# AirPort_V1_0.net
KiCad netlist of a schematic drawn in Altium Designer
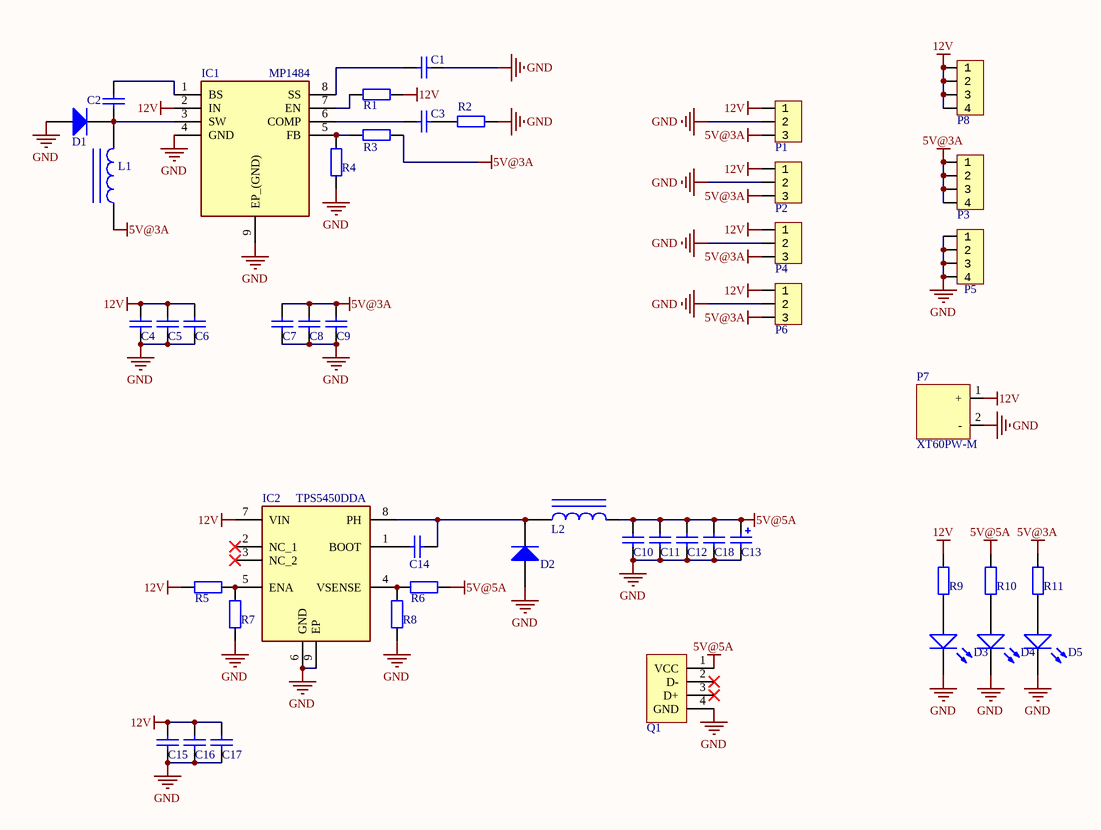
[diagram p0: AirPort_V1.0.SchDoc]

(export (version "E")
  (design (tool "Eeschema 10.0.6"))
  (components
    (comp (ref "C1")
      (value "100nF")
      (footprint "CAP-0603")
      (description "贴片电容")
      (libsource (lib "Power_Lib_Altium") (part "CAP"))
    )
    (comp (ref "C2")
      (value "10nF")
      (footprint "CAP-0603")
      (description "贴片电容")
      (libsource (lib "Power_Lib_Altium") (part "CAP"))
    )
    (comp (ref "C3")
      (value "6.8nF")
      (footprint "CAP-0603")
      (description "贴片电容")
      (libsource (lib "Power_Lib_Altium") (part "CAP"))
    )
    (comp (ref "C4")
      (value "10uF")
      (footprint "CAP-1206")
      (description "贴片电容")
      (libsource (lib "Power_Lib_Altium") (part "CAP"))
    )
    (comp (ref "C5")
      (value "10uF")
      (footprint "CAP-1206")
      (description "贴片电容")
      (libsource (lib "Power_Lib_Altium") (part "CAP"))
    )
    (comp (ref "C6")
      (value "10uF")
      (footprint "CAP-1206")
      (description "贴片电容")
      (libsource (lib "Power_Lib_Altium") (part "CAP"))
    )
    (comp (ref "C7")
      (value "10uF")
      (footprint "CAP-1206")
      (description "贴片电容")
      (libsource (lib "Power_Lib_Altium") (part "CAP"))
    )
    (comp (ref "C8")
      (value "10uF")
      (footprint "CAP-1206")
      (description "贴片电容")
      (libsource (lib "Power_Lib_Altium") (part "CAP"))
    )
    (comp (ref "C9")
      (value "10uF")
      (footprint "CAP-1206")
      (description "贴片电容")
      (libsource (lib "Power_Lib_Altium") (part "CAP"))
    )
    (comp (ref "C10")
      (value "10uF")
      (footprint "CAP-1206")
      (description "贴片电容")
      (libsource (lib "Power_Lib_Altium") (part "CAP"))
    )
    (comp (ref "C11")
      (value "10uF")
      (footprint "CAP-1206")
      (description "贴片电容")
      (libsource (lib "Power_Lib_Altium") (part "CAP"))
    )
    (comp (ref "C12")
      (value "0.01uF")
      (footprint "CAP-0603")
      (description "贴片电容")
      (libsource (lib "Power_Lib_Altium") (part "CAP"))
    )
    (comp (ref "C13")
      (value "330uF")
      (footprint "CAP-2.5*6.3*11.2-H - GD")
      (description "贴片电容-有极性")
      (libsource (lib "Power_Lib_Altium") (part "CAP-POL"))
    )
    (comp (ref "C14")
      (value "0.01uF")
      (footprint "CAP-0603")
      (description "贴片电容")
      (libsource (lib "Power_Lib_Altium") (part "CAP"))
    )
    (comp (ref "C15")
      (value "4.7uF")
      (footprint "CAP-1206")
      (description "贴片电容")
      (libsource (lib "Power_Lib_Altium") (part "CAP"))
    )
    (comp (ref "C16")
      (value "4.7uF")
      (footprint "CAP-1206")
      (description "贴片电容")
      (libsource (lib "Power_Lib_Altium") (part "CAP"))
    )
    (comp (ref "C17")
      (value "0.01uF")
      (footprint "CAP-1206")
      (description "贴片电容")
      (libsource (lib "Power_Lib_Altium") (part "CAP"))
    )
    (comp (ref "C18")
      (value "0.01uF")
      (footprint "CAP-0603")
      (description "贴片电容")
      (libsource (lib "Power_Lib_Altium") (part "CAP"))
    )
    (comp (ref "D1")
      (value "1N4007")
      (footprint "SOD_123")
      (description "M7 二极管")
      (libsource (lib "Power_Lib_Altium") (part "DIODE"))
    )
    (comp (ref "D2")
      (value "B540C")
      (footprint "DO-214AB")
      (description "二极管")
      (libsource (lib "Power_Lib_Altium") (part "DIODE"))
    )
    (comp (ref "D3")
      (value "RED")
      (footprint "LED-0603")
      (description "发光二极管")
      (libsource (lib "Power_Lib_Altium") (part "LED"))
    )
    (comp (ref "D4")
      (value "RED")
      (footprint "LED-0603")
      (description "发光二极管")
      (libsource (lib "Power_Lib_Altium") (part "LED"))
    )
    (comp (ref "D5")
      (value "RED")
      (footprint "LED-0603")
      (description "发光二极管")
      (libsource (lib "Power_Lib_Altium") (part "LED"))
    )
    (comp (ref "IC1")
      (value "MP1484")
      (footprint "SOIC_8_PAD")
      (description "同步降压稳压器")
      (fields
        (field (name "MANUFACTURER_PART_NUMBER") "MP1484EN-LF")
        (field (name "MOUSER PART NUMBER") "946-MP1484ENLF")
      )
      (libsource (lib "Power_Lib_Altium") (part "MP1484"))
    )
    (comp (ref "IC2")
      (value "TPS5450DDA")
      (footprint "SOIC_8_PAD")
      (description "集成稳压芯片")
      (fields (field (name "MOUSER PART NUMBER") "595-TPS5450DDA"))
      (libsource (lib "Power_Lib_Altium") (part "TPS5450DDA"))
    )
    (comp (ref "L1")
      (value "10uH")
      (footprint "XAL6060-103MEB")
      (description "贴片电感 5A")
      (libsource (lib "Power_Lib_Altium") (part "INDUCTOR"))
    )
    (comp (ref "L2")
      (value "15uH")
      (footprint "SMD-13.45x12.6x4.8mm")
      (description "8A 贴片电感CMKD-1350A-150M")
      (libsource (lib "Power_Lib_Altium") (part "INDUCTOR"))
    )
    (comp (ref "P1")
      (value "XH-3AW")
      (footprint "XH_3")
      (description "Header")
      (libsource (lib "Power_Lib_Altium") (part "HDR1x3_2.54"))
    )
    (comp (ref "P2")
      (value "XH-3AW")
      (footprint "XH_3")
      (description "Header")
      (libsource (lib "Power_Lib_Altium") (part "HDR1x3_2.54"))
    )
    (comp (ref "P3")
      (value "HDR1x4_2.54")
      (footprint "HDR1x4_2.54_180")
      (description "Header")
      (libsource (lib "Power_Lib_Altium") (part "HDR1x4_2.54"))
    )
    (comp (ref "P4")
      (value "XH-3AW")
      (footprint "XH_3")
      (description "Header")
      (libsource (lib "Power_Lib_Altium") (part "HDR1x3_2.54"))
    )
    (comp (ref "P5")
      (value "HDR1x4_2.54")
      (footprint "HDR1x4_2.54_180")
      (description "Header")
      (libsource (lib "Power_Lib_Altium") (part "HDR1x4_2.54"))
    )
    (comp (ref "P6")
      (value "XH-3AW")
      (footprint "XH_3")
      (description "Header")
      (libsource (lib "Power_Lib_Altium") (part "HDR1x3_2.54"))
    )
    (comp (ref "P7")
      (value "XT60PW-M")
      (footprint "XT60PW-M")
      (description "XT60")
      (libsource (lib "Hare_Library") (part "XT60"))
    )
    (comp (ref "P8")
      (value "HDR1x4_2.54")
      (footprint "HDR1x4_2.54_180")
      (description "Header")
      (libsource (lib "Power_Lib_Altium") (part "HDR1x4_2.54"))
    )
    (comp (ref "Q1")
      (value "USB A")
      (footprint "USB_A_MALE_4_POS_Solder_RA_SMD_4_Terminal_1_Port")
      (description "USB 接口")
      (libsource (lib "Power_Lib_Altium") (part "USB A"))
    )
    (comp (ref "R1")
      (value "100K")
      (footprint "R-0603")
      (description "贴片电阻")
      (libsource (lib "Power_Lib_Altium") (part "RES"))
    )
    (comp (ref "R2")
      (value "6.8K")
      (footprint "R-0603")
      (description "贴片电阻")
      (libsource (lib "Power_Lib_Altium") (part "RES"))
    )
    (comp (ref "R3")
      (value "44.2K")
      (footprint "R-0603")
      (description "贴片电阻")
      (libsource (lib "Power_Lib_Altium") (part "RES"))
    )
    (comp (ref "R4")
      (value "10K")
      (footprint "R-0603")
      (description "贴片电阻")
      (libsource (lib "") (part "RES_1"))
    )
    (comp (ref "R5")
      (value "15K")
      (footprint "R-0603")
      (description "贴片电阻")
      (libsource (lib "") (part "RES_3"))
    )
    (comp (ref "R6")
      (value "10K")
      (footprint "R-0603")
      (description "贴片电阻")
      (libsource (lib "") (part "RES_3"))
    )
    (comp (ref "R7")
      (value "10K")
      (footprint "R-0603")
      (description "贴片电阻")
      (libsource (lib "") (part "RES_2"))
    )
    (comp (ref "R8")
      (value "3.16K")
      (footprint "R-0603")
      (description "贴片电阻")
      (libsource (lib "") (part "RES_1"))
    )
    (comp (ref "R9")
      (value "10k")
      (footprint "R-0603")
      (description "贴片电阻")
      (libsource (lib "") (part "RES_1"))
    )
    (comp (ref "R10")
      (value "10k")
      (footprint "R-0603")
      (description "贴片电阻")
      (libsource (lib "") (part "RES_1"))
    )
    (comp (ref "R11")
      (value "10k")
      (footprint "R-0603")
      (description "贴片电阻")
      (libsource (lib "") (part "RES_1"))
    )
  )
  (nets
    (net (code "1") (name "5V@3A") (class "Default")
      (node (ref "C7") (pin "2") (pinfunction "2_2") (pintype "passive"))
      (node (ref "C8") (pin "2") (pinfunction "2_2") (pintype "passive"))
      (node (ref "C9") (pin "2") (pinfunction "2_2") (pintype "passive"))
      (node (ref "L1") (pin "1") (pinfunction "1_1") (pintype "passive"))
      (node (ref "P1") (pin "3") (pinfunction "3_3") (pintype "passive"))
      (node (ref "P2") (pin "3") (pinfunction "3_3") (pintype "passive"))
      (node (ref "P3") (pin "1") (pinfunction "1_1") (pintype "passive"))
      (node (ref "P3") (pin "2") (pinfunction "2_2") (pintype "passive"))
      (node (ref "P3") (pin "3") (pinfunction "3_3") (pintype "passive"))
      (node (ref "P3") (pin "4") (pinfunction "4_4") (pintype "passive"))
      (node (ref "P4") (pin "3") (pinfunction "3_3") (pintype "passive"))
      (node (ref "P6") (pin "3") (pinfunction "3_3") (pintype "passive"))
      (node (ref "R11") (pin "2") (pinfunction "2_2") (pintype "passive"))
      (node (ref "R3") (pin "2") (pinfunction "2_2") (pintype "passive"))
    )
    (net (code "2") (name "5V@5A") (class "Default")
      (node (ref "C10") (pin "2") (pinfunction "2_2") (pintype "passive"))
      (node (ref "C11") (pin "2") (pinfunction "2_2") (pintype "passive"))
      (node (ref "C12") (pin "2") (pinfunction "2_2") (pintype "passive"))
      (node (ref "C13") (pin "1") (pinfunction "1_1") (pintype "passive"))
      (node (ref "C18") (pin "2") (pinfunction "2_2") (pintype "passive"))
      (node (ref "L2") (pin "2") (pinfunction "2_2") (pintype "passive"))
      (node (ref "Q1") (pin "1") (pinfunction "VCC_1") (pintype "passive"))
      (node (ref "R10") (pin "2") (pinfunction "2_2") (pintype "passive"))
      (node (ref "R6") (pin "1") (pinfunction "1_1") (pintype "passive"))
    )
    (net (code "3") (name "12V") (class "Default")
      (node (ref "C15") (pin "2") (pinfunction "2_2") (pintype "passive"))
      (node (ref "C16") (pin "2") (pinfunction "2_2") (pintype "passive"))
      (node (ref "C17") (pin "2") (pinfunction "2_2") (pintype "passive"))
      (node (ref "C4") (pin "2") (pinfunction "2_2") (pintype "passive"))
      (node (ref "C5") (pin "2") (pinfunction "2_2") (pintype "passive"))
      (node (ref "C6") (pin "2") (pinfunction "2_2") (pintype "passive"))
      (node (ref "IC1") (pin "2") (pinfunction "IN_2") (pintype "passive"))
      (node (ref "IC2") (pin "7") (pinfunction "VIN_7") (pintype "passive"))
      (node (ref "P1") (pin "1") (pinfunction "1_1") (pintype "passive"))
      (node (ref "P2") (pin "1") (pinfunction "1_1") (pintype "passive"))
      (node (ref "P4") (pin "1") (pinfunction "1_1") (pintype "passive"))
      (node (ref "P6") (pin "1") (pinfunction "1_1") (pintype "passive"))
      (node (ref "P7") (pin "1") (pinfunction "+_1") (pintype "passive"))
      (node (ref "P8") (pin "1") (pinfunction "1_1") (pintype "passive"))
      (node (ref "P8") (pin "2") (pinfunction "2_2") (pintype "passive"))
      (node (ref "P8") (pin "3") (pinfunction "3_3") (pintype "passive"))
      (node (ref "P8") (pin "4") (pinfunction "4_4") (pintype "passive"))
      (node (ref "R1") (pin "2") (pinfunction "2_2") (pintype "passive"))
      (node (ref "R5") (pin "2") (pinfunction "2_2") (pintype "passive"))
      (node (ref "R9") (pin "2") (pinfunction "2_2") (pintype "passive"))
    )
    (net (code "4") (name "GND") (class "Default")
      (node (ref "C1") (pin "1") (pinfunction "1_1") (pintype "passive"))
      (node (ref "C10") (pin "1") (pinfunction "1_1") (pintype "passive"))
      (node (ref "C11") (pin "1") (pinfunction "1_1") (pintype "passive"))
      (node (ref "C12") (pin "1") (pinfunction "1_1") (pintype "passive"))
      (node (ref "C13") (pin "2") (pinfunction "2_2") (pintype "passive"))
      (node (ref "C15") (pin "1") (pinfunction "1_1") (pintype "passive"))
      (node (ref "C16") (pin "1") (pinfunction "1_1") (pintype "passive"))
      (node (ref "C17") (pin "1") (pinfunction "1_1") (pintype "passive"))
      (node (ref "C18") (pin "1") (pinfunction "1_1") (pintype "passive"))
      (node (ref "C4") (pin "1") (pinfunction "1_1") (pintype "passive"))
      (node (ref "C5") (pin "1") (pinfunction "1_1") (pintype "passive"))
      (node (ref "C6") (pin "1") (pinfunction "1_1") (pintype "passive"))
      (node (ref "C7") (pin "1") (pinfunction "1_1") (pintype "passive"))
      (node (ref "C8") (pin "1") (pinfunction "1_1") (pintype "passive"))
      (node (ref "C9") (pin "1") (pinfunction "1_1") (pintype "passive"))
      (node (ref "D1") (pin "1") (pinfunction "A_1") (pintype "passive"))
      (node (ref "D2") (pin "1") (pinfunction "A_1") (pintype "passive"))
      (node (ref "D3") (pin "K") (pinfunction "K_K") (pintype "passive"))
      (node (ref "D4") (pin "K") (pinfunction "K_K") (pintype "passive"))
      (node (ref "D5") (pin "K") (pinfunction "K_K") (pintype "passive"))
      (node (ref "IC1") (pin "4") (pinfunction "GND_4") (pintype "passive"))
      (node (ref "IC1") (pin "9") (pinfunction "EP_(GND)_9") (pintype "passive"))
      (node (ref "IC2") (pin "6") (pinfunction "GND_6") (pintype "passive"))
      (node (ref "IC2") (pin "9") (pinfunction "EP_9") (pintype "passive"))
      (node (ref "P1") (pin "2") (pinfunction "2_2") (pintype "passive"))
      (node (ref "P2") (pin "2") (pinfunction "2_2") (pintype "passive"))
      (node (ref "P4") (pin "2") (pinfunction "2_2") (pintype "passive"))
      (node (ref "P5") (pin "1") (pinfunction "1_1") (pintype "passive"))
      (node (ref "P5") (pin "2") (pinfunction "2_2") (pintype "passive"))
      (node (ref "P5") (pin "3") (pinfunction "3_3") (pintype "passive"))
      (node (ref "P5") (pin "4") (pinfunction "4_4") (pintype "passive"))
      (node (ref "P6") (pin "2") (pinfunction "2_2") (pintype "passive"))
      (node (ref "P7") (pin "2") (pinfunction "-_2") (pintype "passive"))
      (node (ref "Q1") (pin "4") (pinfunction "GND_4") (pintype "passive"))
      (node (ref "R2") (pin "2") (pinfunction "2_2") (pintype "passive"))
      (node (ref "R4") (pin "1") (pinfunction "1_1") (pintype "passive"))
      (node (ref "R7") (pin "2") (pinfunction "2_2") (pintype "passive"))
      (node (ref "R8") (pin "1") (pinfunction "1_1") (pintype "passive"))
    )
    (net (code "5") (name "Net-(C3-Pad1)") (class "Default")
      (node (ref "C3") (pin "1") (pinfunction "1_1") (pintype "passive"))
      (node (ref "R2") (pin "1") (pinfunction "1_1") (pintype "passive"))
    )
    (net (code "6") (name "Net-(D1-K)") (class "Default")
      (node (ref "C2") (pin "1") (pinfunction "1_1") (pintype "passive"))
      (node (ref "D1") (pin "2") (pinfunction "K_2") (pintype "passive"))
      (node (ref "IC1") (pin "3") (pinfunction "SW_3") (pintype "passive"))
      (node (ref "L1") (pin "2") (pinfunction "2_2") (pintype "passive"))
    )
    (net (code "7") (name "Net-(D2-K)") (class "Default")
      (node (ref "C14") (pin "1") (pinfunction "1_1") (pintype "passive"))
      (node (ref "D2") (pin "2") (pinfunction "K_2") (pintype "passive"))
      (node (ref "IC2") (pin "8") (pinfunction "PH_8") (pintype "passive"))
      (node (ref "L2") (pin "1") (pinfunction "1_1") (pintype "passive"))
    )
    (net (code "8") (name "Net-(D3-PadA)") (class "Default")
      (node (ref "D3") (pin "A") (pinfunction "A_A") (pintype "passive"))
      (node (ref "R9") (pin "1") (pinfunction "1_1") (pintype "passive"))
    )
    (net (code "9") (name "Net-(D4-PadA)") (class "Default")
      (node (ref "D4") (pin "A") (pinfunction "A_A") (pintype "passive"))
      (node (ref "R10") (pin "1") (pinfunction "1_1") (pintype "passive"))
    )
    (net (code "10") (name "Net-(D5-PadA)") (class "Default")
      (node (ref "D5") (pin "A") (pinfunction "A_A") (pintype "passive"))
      (node (ref "R11") (pin "1") (pinfunction "1_1") (pintype "passive"))
    )
    (net (code "11") (name "Net-(IC1-BS)") (class "Default")
      (node (ref "C2") (pin "2") (pinfunction "2_2") (pintype "passive"))
      (node (ref "IC1") (pin "1") (pinfunction "BS_1") (pintype "passive"))
    )
    (net (code "12") (name "Net-(IC1-COMP)") (class "Default")
      (node (ref "C3") (pin "2") (pinfunction "2_2") (pintype "passive"))
      (node (ref "IC1") (pin "6") (pinfunction "COMP_6") (pintype "passive"))
    )
    (net (code "13") (name "Net-(IC1-EN)") (class "Default")
      (node (ref "IC1") (pin "7") (pinfunction "EN_7") (pintype "passive"))
      (node (ref "R1") (pin "1") (pinfunction "1_1") (pintype "passive"))
    )
    (net (code "14") (name "Net-(IC1-FB)") (class "Default")
      (node (ref "IC1") (pin "5") (pinfunction "FB_5") (pintype "passive"))
      (node (ref "R3") (pin "1") (pinfunction "1_1") (pintype "passive"))
      (node (ref "R4") (pin "2") (pinfunction "2_2") (pintype "passive"))
    )
    (net (code "15") (name "Net-(IC1-SS)") (class "Default")
      (node (ref "C1") (pin "2") (pinfunction "2_2") (pintype "passive"))
      (node (ref "IC1") (pin "8") (pinfunction "SS_8") (pintype "passive"))
    )
    (net (code "16") (name "Net-(IC2-BOOT)") (class "Default")
      (node (ref "C14") (pin "2") (pinfunction "2_2") (pintype "passive"))
      (node (ref "IC2") (pin "1") (pinfunction "BOOT_1") (pintype "passive"))
    )
    (net (code "17") (name "Net-(IC2-ENA)") (class "Default")
      (node (ref "IC2") (pin "5") (pinfunction "ENA_5") (pintype "passive"))
      (node (ref "R5") (pin "1") (pinfunction "1_1") (pintype "passive"))
      (node (ref "R7") (pin "1") (pinfunction "1_1") (pintype "passive"))
    )
    (net (code "18") (name "Net-(IC2-VSENSE)") (class "Default")
      (node (ref "IC2") (pin "4") (pinfunction "VSENSE_4") (pintype "passive"))
      (node (ref "R6") (pin "2") (pinfunction "2_2") (pintype "passive"))
      (node (ref "R8") (pin "2") (pinfunction "2_2") (pintype "passive"))
    )
    (net (code "19") (name "unconnected-(IC2-NC_1-Pad2)") (class "Default")
      (node (ref "IC2") (pin "2") (pinfunction "NC_1_2") (pintype "passive+no_connect"))
    )
    (net (code "20") (name "unconnected-(IC2-NC_2-Pad3)") (class "Default")
      (node (ref "IC2") (pin "3") (pinfunction "NC_2_3") (pintype "passive+no_connect"))
    )
    (net (code "21") (name "unconnected-(Q1-D+-Pad3)") (class "Default")
      (node (ref "Q1") (pin "3") (pinfunction "D+_3") (pintype "passive+no_connect"))
    )
    (net (code "22") (name "unconnected-(Q1-D--Pad2)") (class "Default")
      (node (ref "Q1") (pin "2") (pinfunction "D-_2") (pintype "passive+no_connect"))
    )
  )
)
